# humidity.net
KiCad netlist of a schematic drawn in Altium Designer
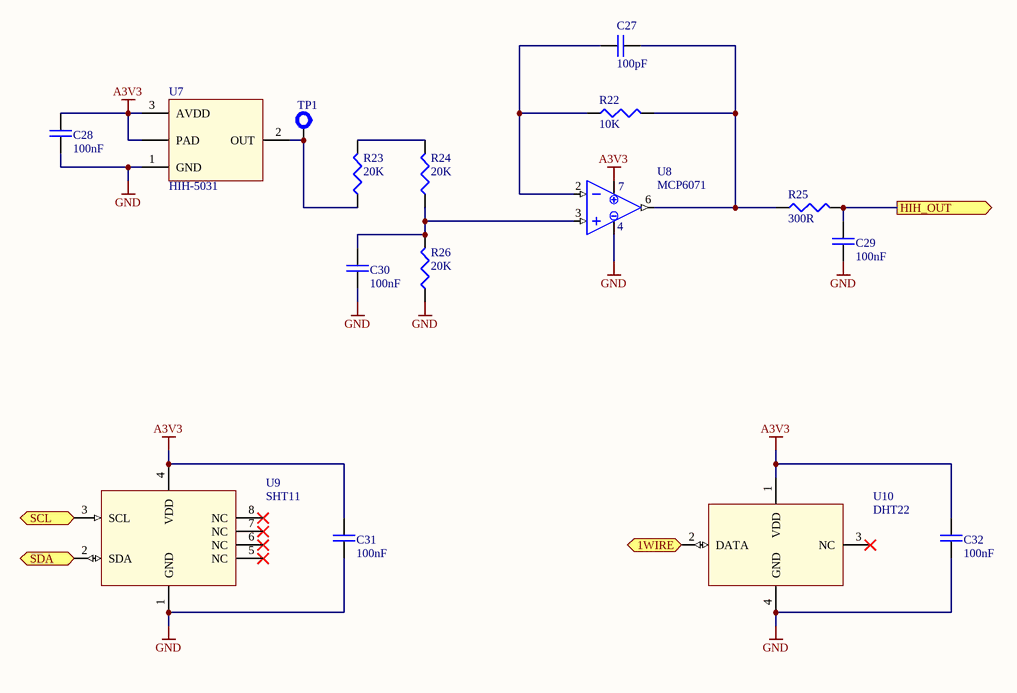
[diagram p0: humidity.SchDoc]

(export (version "E")
  (design (tool "Eeschema 10.0.6"))
  (components
    (comp (ref "C27")
      (value "100pF")
      (footprint "0603")
      (description "Capacitor")
      (fields (field (name "OWNER") "Nuno Brum"))
      (libsource (lib "Alcetronics_Devices") (part "CAP"))
    )
    (comp (ref "C28")
      (value "100nF")
      (footprint "0603")
      (description "Capacitor")
      (fields (field (name "OWNER") "Nuno Brum"))
      (libsource (lib "Alcetronics_Devices") (part "CAP"))
    )
    (comp (ref "C29")
      (value "100nF")
      (footprint "0603")
      (description "Capacitor")
      (fields (field (name "OWNER") "Nuno Brum"))
      (libsource (lib "Alcetronics_Devices") (part "CAP"))
    )
    (comp (ref "C30")
      (value "100nF")
      (footprint "0603")
      (description "Capacitor")
      (fields (field (name "OWNER") "Nuno Brum"))
      (libsource (lib "Alcetronics_Devices") (part "CAP"))
    )
    (comp (ref "C31")
      (value "100nF")
      (footprint "0603")
      (description "Capacitor")
      (fields (field (name "OWNER") "Nuno Brum"))
      (libsource (lib "Alcetronics_Devices") (part "CAP"))
    )
    (comp (ref "C32")
      (value "100nF")
      (footprint "0603")
      (description "Capacitor")
      (fields (field (name "OWNER") "Nuno Brum"))
      (libsource (lib "Alcetronics_Devices") (part "CAP"))
    )
    (comp (ref "R22")
      (value "10K")
      (footprint "0603")
      (description "Resistor")
      (fields (field (name "OWNER") "Nuno Brum"))
      (libsource (lib "Alcetronics_Devices") (part "RES"))
    )
    (comp (ref "R23")
      (value "20K")
      (footprint "0603")
      (description "Resistor")
      (fields (field (name "OWNER") "Nuno Brum"))
      (libsource (lib "Alcetronics_Devices") (part "RES"))
    )
    (comp (ref "R24")
      (value "20K")
      (footprint "0603")
      (description "Resistor")
      (fields (field (name "OWNER") "Nuno Brum"))
      (libsource (lib "Alcetronics_Devices") (part "RES"))
    )
    (comp (ref "R25")
      (value "300R")
      (footprint "0603")
      (description "Resistor")
      (fields (field (name "OWNER") "Nuno Brum"))
      (libsource (lib "Alcetronics_Devices") (part "RES"))
    )
    (comp (ref "R26")
      (value "20K")
      (footprint "0603")
      (description "Resistor")
      (fields (field (name "OWNER") "Nuno Brum"))
      (libsource (lib "Alcetronics_Devices") (part "RES"))
    )
    (comp (ref "TP1")
      (value "Test Point")
      (footprint "TERMINAL")
      (description "Test/Probe Point")
      (fields (field (name "OWNER") "Nuno Brum"))
      (libsource (lib "Alcetronics_EM") (part "TEST-PROBE"))
    )
    (comp (ref "U7")
      (value "HIH-5031")
      (footprint "HIH")
      (description "Low Voltage Humidity Sensor")
      (libsource (lib "Alcetronics_IC") (part "HIH-5031"))
    )
    (comp (ref "U8")
      (value "MCP6071")
      (footprint "SOIC-8")
      (description "Low-Offset Opamp")
      (libsource (lib "Alcetronics_IC") (part "MCP6V26"))
    )
    (comp (ref "U9")
      (value "SHT11")
      (footprint "SHT")
      (description "Digital Humidity and Temperature Sensor")
      (libsource (lib "Alcetronics_IC") (part "SHT11"))
    )
    (comp (ref "U10")
      (value "DHT22")
      (footprint "DHT22")
      (description "Digital Humidity and Temperature Sensor")
      (libsource (lib "Alcetronics_IC") (part "DHT22"))
    )
  )
  (nets
    (net (code "1") (name "/1WIRE") (class "Default")
      (node (ref "U10") (pin "2") (pinfunction "DATA_2") (pintype "bidirectional"))
    )
    (net (code "2") (name "/HIH_OUT") (class "Default")
      (node (ref "C29") (pin "2") (pinfunction "2_2") (pintype "passive"))
      (node (ref "R25") (pin "2") (pinfunction "2_2") (pintype "passive"))
    )
    (net (code "3") (name "/SCL") (class "Default")
      (node (ref "U9") (pin "3") (pinfunction "SCL_3") (pintype "input"))
    )
    (net (code "4") (name "/SDA") (class "Default")
      (node (ref "U9") (pin "2") (pinfunction "SDA_2") (pintype "bidirectional"))
    )
    (net (code "5") (name "A3V3") (class "Default")
      (node (ref "C28") (pin "2") (pinfunction "2_2") (pintype "passive"))
      (node (ref "C31") (pin "2") (pinfunction "2_2") (pintype "passive"))
      (node (ref "C32") (pin "2") (pinfunction "2_2") (pintype "passive"))
      (node (ref "U10") (pin "1") (pinfunction "VDD_1") (pintype "power_in"))
      (node (ref "U7") (pin "3") (pinfunction "AVDD_3") (pintype "power_in"))
      (node (ref "U7") (pin "PAD") (pinfunction "PAD_PAD") (pintype "passive"))
      (node (ref "U8") (pin "7") (pinfunction "VDD_7") (pintype "power_in"))
      (node (ref "U9") (pin "4") (pinfunction "VDD_4") (pintype "power_in"))
    )
    (net (code "6") (name "GND") (class "Default")
      (node (ref "C28") (pin "1") (pinfunction "1_1") (pintype "passive"))
      (node (ref "C29") (pin "1") (pinfunction "1_1") (pintype "passive"))
      (node (ref "C30") (pin "1") (pinfunction "1_1") (pintype "passive"))
      (node (ref "C31") (pin "1") (pinfunction "1_1") (pintype "passive"))
      (node (ref "C32") (pin "1") (pinfunction "1_1") (pintype "passive"))
      (node (ref "R26") (pin "1") (pinfunction "1_1") (pintype "passive"))
      (node (ref "U10") (pin "4") (pinfunction "GND_4") (pintype "power_in"))
      (node (ref "U7") (pin "1") (pinfunction "GND_1") (pintype "power_in"))
      (node (ref "U8") (pin "4") (pinfunction "VSS_4") (pintype "power_in"))
      (node (ref "U9") (pin "1") (pinfunction "GND_1") (pintype "power_in"))
    )
    (net (code "7") (name "Net-(R23-Pad2)") (class "Default")
      (node (ref "R23") (pin "2") (pinfunction "2_2") (pintype "passive"))
      (node (ref "R24") (pin "2") (pinfunction "2_2") (pintype "passive"))
    )
    (net (code "8") (name "Net-(TP1-TP)") (class "Default")
      (node (ref "R23") (pin "1") (pinfunction "1_1") (pintype "passive"))
      (node (ref "TP1") (pin "1") (pinfunction "TP_1") (pintype "passive"))
      (node (ref "U7") (pin "2") (pinfunction "OUT_2") (pintype "passive"))
    )
    (net (code "9") (name "Net-(U8-INN)") (class "Default")
      (node (ref "C27") (pin "1") (pinfunction "1_1") (pintype "passive"))
      (node (ref "R22") (pin "1") (pinfunction "1_1") (pintype "passive"))
      (node (ref "U8") (pin "2") (pinfunction "INN_2") (pintype "input"))
    )
    (net (code "10") (name "Net-(U8-INP)") (class "Default")
      (node (ref "C30") (pin "2") (pinfunction "2_2") (pintype "passive"))
      (node (ref "R24") (pin "1") (pinfunction "1_1") (pintype "passive"))
      (node (ref "R26") (pin "2") (pinfunction "2_2") (pintype "passive"))
      (node (ref "U8") (pin "3") (pinfunction "INP_3") (pintype "input"))
    )
    (net (code "11") (name "Net-(U8-VOUT)") (class "Default")
      (node (ref "C27") (pin "2") (pinfunction "2_2") (pintype "passive"))
      (node (ref "R22") (pin "2") (pinfunction "2_2") (pintype "passive"))
      (node (ref "R25") (pin "1") (pinfunction "1_1") (pintype "passive"))
      (node (ref "U8") (pin "6") (pinfunction "VOUT_6") (pintype "output"))
    )
    (net (code "12") (name "unconnected-(U9-NC-Pad5)") (class "Default")
      (node (ref "U9") (pin "5") (pinfunction "NC_5") (pintype "passive+no_connect"))
    )
    (net (code "13") (name "unconnected-(U9-NC-Pad6)") (class "Default")
      (node (ref "U9") (pin "6") (pinfunction "NC_6") (pintype "passive+no_connect"))
    )
    (net (code "14") (name "unconnected-(U9-NC-Pad7)") (class "Default")
      (node (ref "U9") (pin "7") (pinfunction "NC_7") (pintype "passive+no_connect"))
    )
    (net (code "15") (name "unconnected-(U9-NC-Pad8)") (class "Default")
      (node (ref "U9") (pin "8") (pinfunction "NC_8") (pintype "passive+no_connect"))
    )
    (net (code "16") (name "unconnected-(U10-NC-Pad3)") (class "Default")
      (node (ref "U10") (pin "3") (pinfunction "NC_3") (pintype "power_in+no_connect"))
    )
  )
)
